# AutonomousSensorBoard_V1.net
KiCad netlist of a schematic drawn in EAGLE
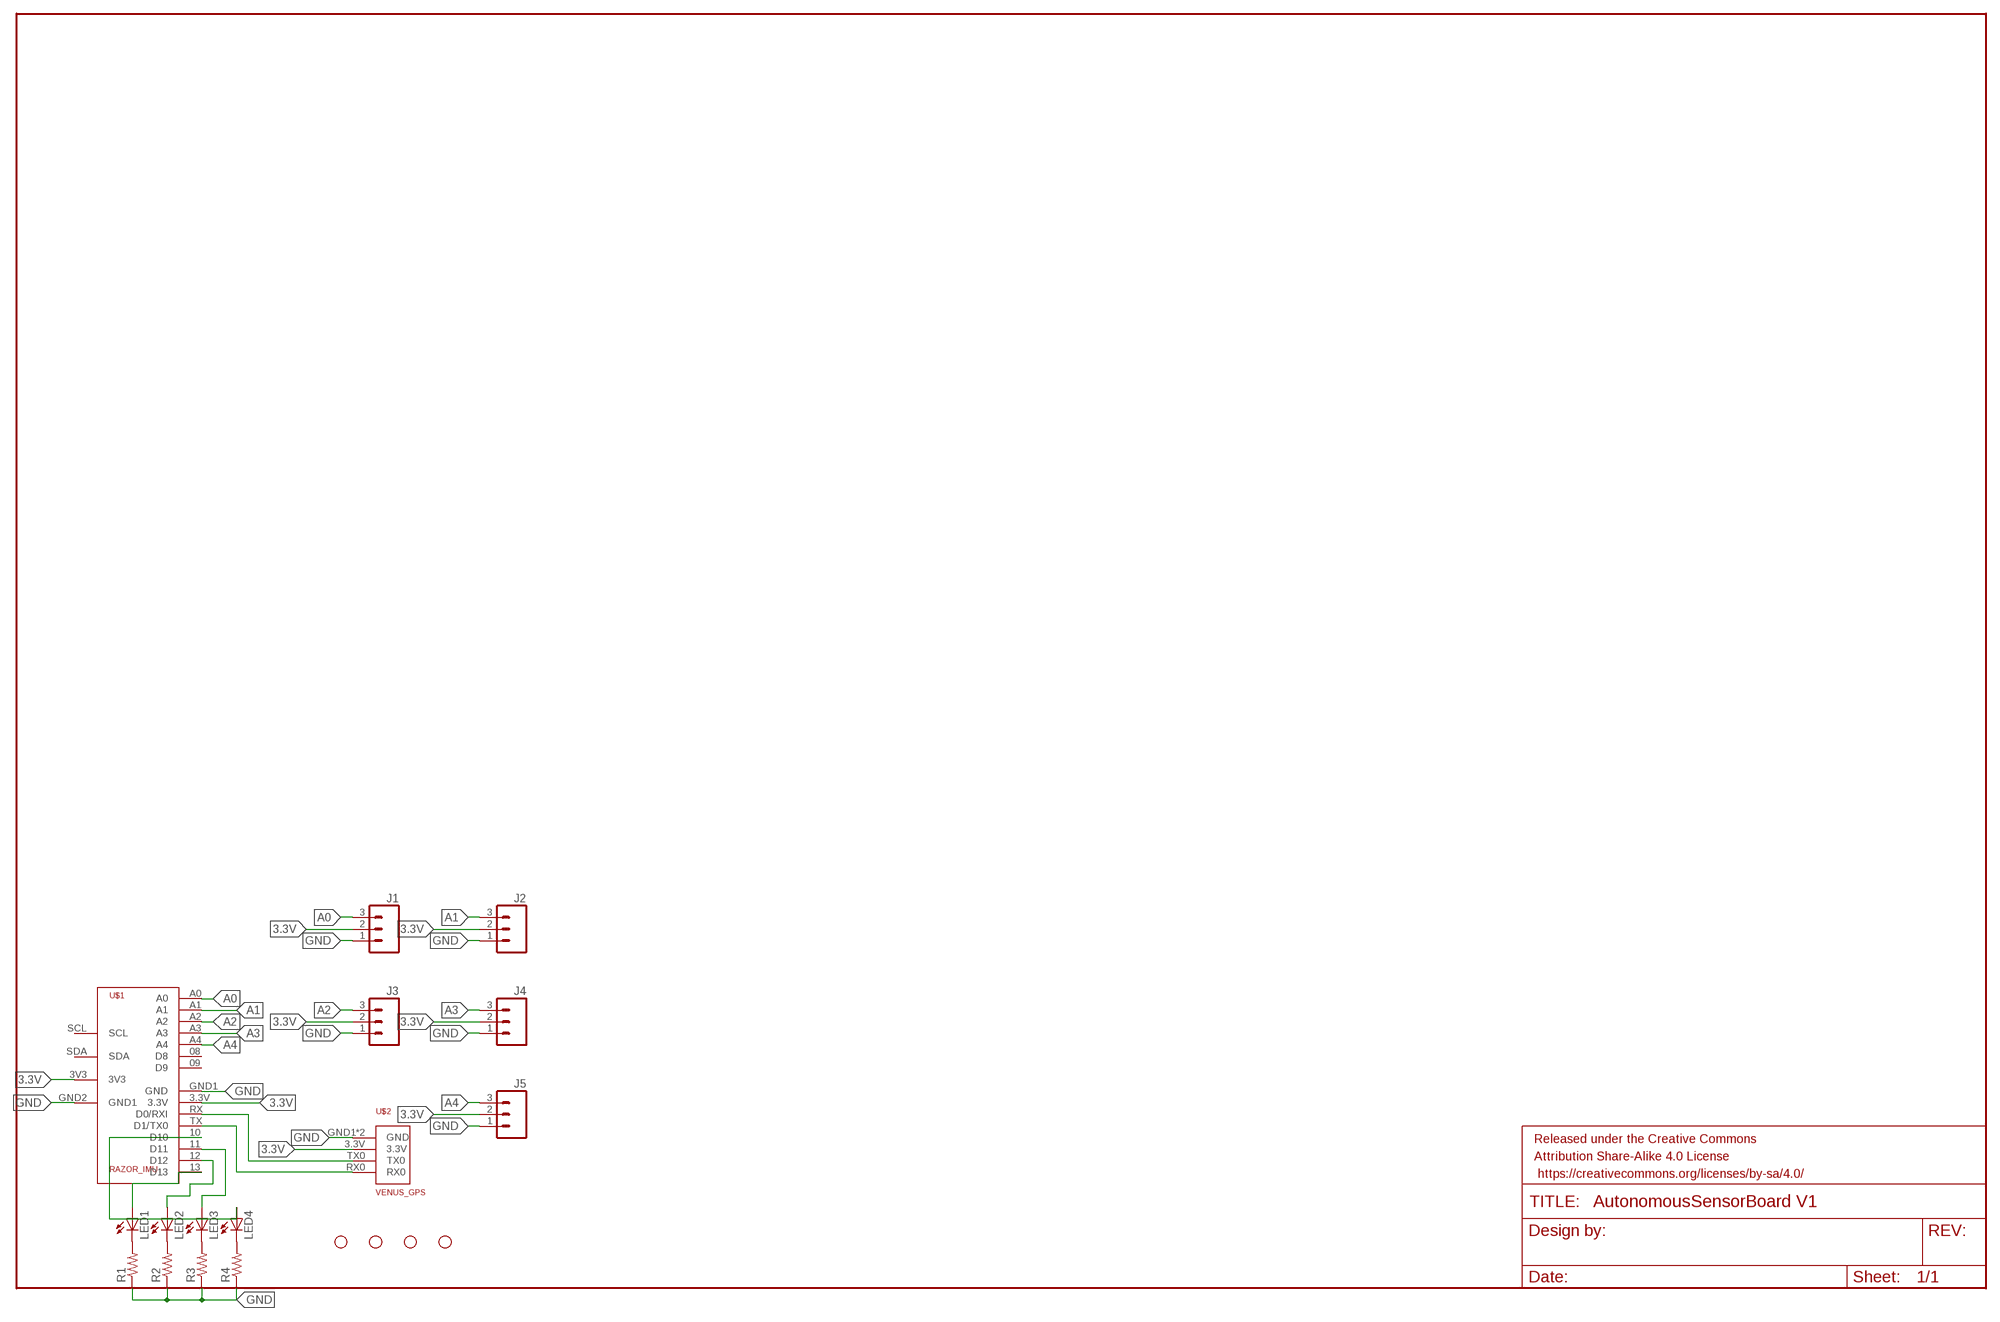
[diagram p0: schematic, sheet 1]

(export (version "E")
  (design (tool "Eeschema 10.0.6"))
  (components
    (comp (ref "FRAME1")
      (value "FRAME-LEDGER")
      (footprint "eagle-import:CREATIVE_COMMONS")
      (libsource (lib "eagle-import") (part "FRAME-LEDGER"))
    )
    (comp (ref "H1")
      (value "STAND-OFF")
      (footprint "eagle-import:STAND-OFF")
      (libsource (lib "eagle-import") (part "STAND-OFF"))
    )
    (comp (ref "H2")
      (value "STAND-OFF")
      (footprint "eagle-import:STAND-OFF")
      (libsource (lib "eagle-import") (part "STAND-OFF"))
    )
    (comp (ref "H3")
      (value "STAND-OFF")
      (footprint "eagle-import:STAND-OFF")
      (libsource (lib "eagle-import") (part "STAND-OFF"))
    )
    (comp (ref "H4")
      (value "STAND-OFF")
      (footprint "eagle-import:STAND-OFF")
      (libsource (lib "eagle-import") (part "STAND-OFF"))
    )
    (comp (ref "J1")
      (value "M03LOCK")
      (footprint "eagle-import:1X03_LOCK")
      (libsource (lib "eagle-import") (part "M03LOCK"))
    )
    (comp (ref "J2")
      (value "M03LOCK")
      (footprint "eagle-import:1X03_LOCK")
      (libsource (lib "eagle-import") (part "M03LOCK"))
    )
    (comp (ref "J3")
      (value "M03LOCK")
      (footprint "eagle-import:1X03_LOCK")
      (libsource (lib "eagle-import") (part "M03LOCK"))
    )
    (comp (ref "J4")
      (value "M03LOCK")
      (footprint "eagle-import:1X03_LOCK")
      (libsource (lib "eagle-import") (part "M03LOCK"))
    )
    (comp (ref "J5")
      (value "M03LOCK")
      (footprint "eagle-import:1X03_LOCK")
      (libsource (lib "eagle-import") (part "M03LOCK"))
    )
    (comp (ref "LED1")
      (value "LEDCHIP-LED0805")
      (footprint "eagle-import:CHIP-LED0805")
      (libsource (lib "eagle-import") (part "LEDCHIP-LED0805"))
    )
    (comp (ref "LED2")
      (value "LEDCHIP-LED0805")
      (footprint "eagle-import:CHIP-LED0805")
      (libsource (lib "eagle-import") (part "LEDCHIP-LED0805"))
    )
    (comp (ref "LED3")
      (value "LEDCHIP-LED0805")
      (footprint "eagle-import:CHIP-LED0805")
      (libsource (lib "eagle-import") (part "LEDCHIP-LED0805"))
    )
    (comp (ref "LED4")
      (value "LEDCHIP-LED0805")
      (footprint "eagle-import:CHIP-LED0805")
      (libsource (lib "eagle-import") (part "LEDCHIP-LED0805"))
    )
    (comp (ref "R1")
      (value "R-US_M0805")
      (footprint "eagle-import:M0805")
      (libsource (lib "eagle-import") (part "R-US_M0805"))
    )
    (comp (ref "R2")
      (value "R-US_M0805")
      (footprint "eagle-import:M0805")
      (libsource (lib "eagle-import") (part "R-US_M0805"))
    )
    (comp (ref "R3")
      (value "R-US_M0805")
      (footprint "eagle-import:M0805")
      (libsource (lib "eagle-import") (part "R-US_M0805"))
    )
    (comp (ref "R4")
      (value "R-US_M0805")
      (footprint "eagle-import:M0805")
      (libsource (lib "eagle-import") (part "R-US_M0805"))
    )
    (comp (ref "U$1")
      (value "RAZOR_IMU")
      (footprint "eagle-import:RAZOR_IMU")
      (libsource (lib "eagle-import") (part "RAZOR_IMU"))
    )
    (comp (ref "U$2")
      (value "VENUS_GPS")
      (footprint "eagle-import:VENUS_GPS")
      (libsource (lib "eagle-import") (part "VENUS_GPS"))
    )
  )
  (nets
    (net (code "1") (name "3.3V") (class "Default")
      (node (ref "J1") (pin "2") (pinfunction "2_2") (pintype "passive"))
      (node (ref "J2") (pin "2") (pinfunction "2_2") (pintype "passive"))
      (node (ref "J3") (pin "2") (pinfunction "2_2") (pintype "passive"))
      (node (ref "J4") (pin "2") (pinfunction "2_2") (pintype "passive"))
      (node (ref "J5") (pin "2") (pinfunction "2_2") (pintype "passive"))
      (node (ref "U$1") (pin "3.3V") (pinfunction "3.3V_3.3V") (pintype "bidirectional"))
      (node (ref "U$1") (pin "3V3") (pinfunction "3V3_3V3") (pintype "bidirectional"))
      (node (ref "U$2") (pin "3.3V") (pinfunction "3.3V_3.3V") (pintype "bidirectional"))
    )
    (net (code "2") (name "A0") (class "Default")
      (node (ref "J1") (pin "3") (pinfunction "3_3") (pintype "passive"))
      (node (ref "U$1") (pin "A0") (pinfunction "A0_A0") (pintype "bidirectional"))
    )
    (net (code "3") (name "A1") (class "Default")
      (node (ref "J2") (pin "3") (pinfunction "3_3") (pintype "passive"))
      (node (ref "U$1") (pin "A1") (pinfunction "A1_A1") (pintype "bidirectional"))
    )
    (net (code "4") (name "A2") (class "Default")
      (node (ref "J3") (pin "3") (pinfunction "3_3") (pintype "passive"))
      (node (ref "U$1") (pin "A2") (pinfunction "A2_A2") (pintype "bidirectional"))
    )
    (net (code "5") (name "A3") (class "Default")
      (node (ref "J4") (pin "3") (pinfunction "3_3") (pintype "passive"))
      (node (ref "U$1") (pin "A3") (pinfunction "A3_A3") (pintype "bidirectional"))
    )
    (net (code "6") (name "A4") (class "Default")
      (node (ref "J5") (pin "3") (pinfunction "3_3") (pintype "passive"))
      (node (ref "U$1") (pin "A4") (pinfunction "A4_A4") (pintype "bidirectional"))
    )
    (net (code "7") (name "GND") (class "Default")
      (node (ref "J1") (pin "1") (pinfunction "1_1") (pintype "passive"))
      (node (ref "J2") (pin "1") (pinfunction "1_1") (pintype "passive"))
      (node (ref "J3") (pin "1") (pinfunction "1_1") (pintype "passive"))
      (node (ref "J4") (pin "1") (pinfunction "1_1") (pintype "passive"))
      (node (ref "J5") (pin "1") (pinfunction "1_1") (pintype "passive"))
      (node (ref "R1") (pin "1") (pinfunction "1_1") (pintype "passive"))
      (node (ref "R2") (pin "1") (pinfunction "1_1") (pintype "passive"))
      (node (ref "R3") (pin "1") (pinfunction "1_1") (pintype "passive"))
      (node (ref "R4") (pin "1") (pinfunction "1_1") (pintype "passive"))
      (node (ref "U$1") (pin "GND1") (pinfunction "GND_GND1") (pintype "bidirectional"))
      (node (ref "U$1") (pin "GND2") (pinfunction "GND1_GND2") (pintype "bidirectional"))
      (node (ref "U$2") (pin "GND1") (pinfunction "GND_GND1") (pintype "bidirectional"))
      (node (ref "U$2") (pin "GND2") (pinfunction "GND_GND2") (pintype "bidirectional"))
    )
    (net (code "8") (name "Net-(LED1-PadC)") (class "Default")
      (node (ref "LED1") (pin "C") (pinfunction "C_C") (pintype "passive"))
      (node (ref "R1") (pin "2") (pinfunction "2_2") (pintype "passive"))
    )
    (net (code "9") (name "Net-(LED2-PadC)") (class "Default")
      (node (ref "LED2") (pin "C") (pinfunction "C_C") (pintype "passive"))
      (node (ref "R2") (pin "2") (pinfunction "2_2") (pintype "passive"))
    )
    (net (code "10") (name "Net-(LED3-PadC)") (class "Default")
      (node (ref "LED3") (pin "C") (pinfunction "C_C") (pintype "passive"))
      (node (ref "R3") (pin "2") (pinfunction "2_2") (pintype "passive"))
    )
    (net (code "11") (name "Net-(LED4-PadC)") (class "Default")
      (node (ref "LED4") (pin "C") (pinfunction "C_C") (pintype "passive"))
      (node (ref "R4") (pin "2") (pinfunction "2_2") (pintype "passive"))
    )
    (net (code "12") (name "Net-(U$1-D0{slash}RXI)") (class "Default")
      (node (ref "U$1") (pin "RX") (pinfunction "D0/RXI_RX") (pintype "bidirectional"))
      (node (ref "U$2") (pin "TX0") (pinfunction "TX0_TX0") (pintype "bidirectional"))
    )
    (net (code "13") (name "Net-(U$1-D1{slash}TX0)") (class "Default")
      (node (ref "U$1") (pin "TX") (pinfunction "D1/TX0_TX") (pintype "bidirectional"))
      (node (ref "U$2") (pin "RX0") (pinfunction "RX0_RX0") (pintype "bidirectional"))
    )
    (net (code "14") (name "Net-(U$1-D10)") (class "Default")
      (node (ref "LED4") (pin "A") (pinfunction "A_A") (pintype "passive"))
      (node (ref "U$1") (pin "10") (pinfunction "D10_10") (pintype "bidirectional"))
    )
    (net (code "15") (name "Net-(U$1-D11)") (class "Default")
      (node (ref "LED3") (pin "A") (pinfunction "A_A") (pintype "passive"))
      (node (ref "U$1") (pin "11") (pinfunction "D11_11") (pintype "bidirectional"))
    )
    (net (code "16") (name "Net-(U$1-D12)") (class "Default")
      (node (ref "LED2") (pin "A") (pinfunction "A_A") (pintype "passive"))
      (node (ref "U$1") (pin "12") (pinfunction "D12_12") (pintype "bidirectional"))
    )
    (net (code "17") (name "Net-(U$1-D13)") (class "Default")
      (node (ref "LED1") (pin "A") (pinfunction "A_A") (pintype "passive"))
      (node (ref "U$1") (pin "13") (pinfunction "D13_13") (pintype "bidirectional"))
    )
    (net (code "18") (name "unconnected-(U$1-D8-Pad08)") (class "Default")
      (node (ref "U$1") (pin "08") (pinfunction "D8_08") (pintype "bidirectional"))
    )
    (net (code "19") (name "unconnected-(U$1-D9-Pad09)") (class "Default")
      (node (ref "U$1") (pin "09") (pinfunction "D9_09") (pintype "bidirectional"))
    )
    (net (code "20") (name "unconnected-(U$1-PadSCL)") (class "Default")
      (node (ref "U$1") (pin "SCL") (pinfunction "SCL_SCL") (pintype "bidirectional"))
    )
    (net (code "21") (name "unconnected-(U$1-PadSDA)") (class "Default")
      (node (ref "U$1") (pin "SDA") (pinfunction "SDA_SDA") (pintype "bidirectional"))
    )
  )
)
